# PWM_schematic_2022-05-03.net
KiCad netlist of a schematic drawn in Altium Designer
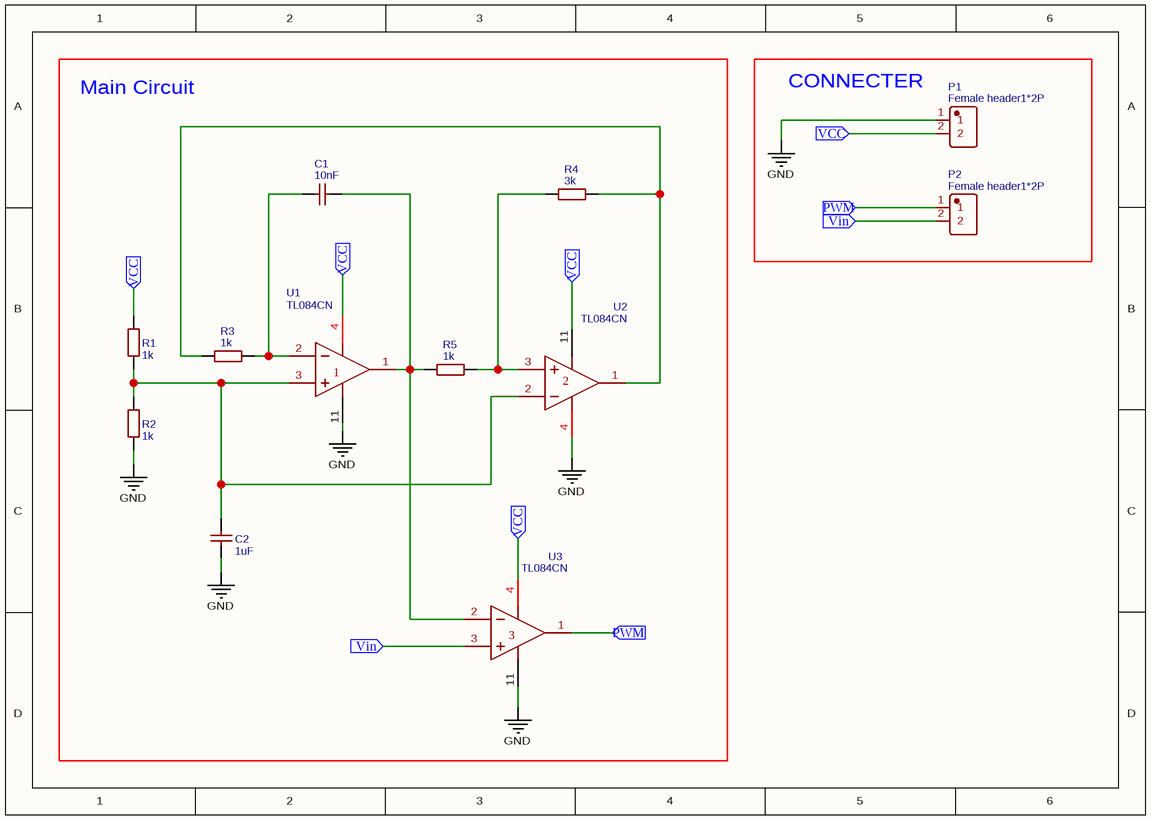
[diagram p0: PWM_schematic_2022-05-03.schdoc]

(export (version "E")
  (design (tool "Eeschema 10.0.6"))
  (components
    (comp (ref "C1")
      (value "10nF")
      (fields
        (field (name "BOM_MANUFACTURER PART") "22pf/50V 10%")
        (field (name "BOM_SUPPLIER PART") "C9316")
      )
      (libsource (lib "altium-import") (part "root_0_10nF_"))
    )
    (comp (ref "C2")
      (value "1uF")
      (fields
        (field (name "BOM_MANUFACTURER PART") "22pf/50V 10%")
        (field (name "BOM_SUPPLIER PART") "C9316")
      )
      (libsource (lib "altium-import") (part "root_1_1uF_"))
    )
    (comp (ref "P1")
      (value "Female header1*2P")
      (fields (field (name "BOM_SUPPLIER PART") "C66509"))
      (libsource (lib "altium-import") (part "root_0_Female header1*2P_"))
    )
    (comp (ref "P2")
      (value "Female header1*2P")
      (fields (field (name "BOM_SUPPLIER PART") "C66509"))
      (libsource (lib "altium-import") (part "root_0_Female header1*2P_"))
    )
    (comp (ref "R1")
      (value "1k")
      (fields
        (field (name "POWER") "1/4W")
        (field (name "TOLERANCE") "±1%")
        (field (name "BOM_SUPPLIER PART") "E57439")
      )
      (libsource (lib "altium-import") (part "root_1_1k_"))
    )
    (comp (ref "R2")
      (value "1k")
      (fields
        (field (name "POWER") "1/4W")
        (field (name "TOLERANCE") "±1%")
        (field (name "BOM_SUPPLIER PART") "E57439")
      )
      (libsource (lib "altium-import") (part "root_1_1k_"))
    )
    (comp (ref "R3")
      (value "1k")
      (fields
        (field (name "POWER") "1/4W")
        (field (name "TOLERANCE") "±1%")
        (field (name "BOM_SUPPLIER PART") "E57439")
      )
      (libsource (lib "altium-import") (part "root_0_1k_"))
    )
    (comp (ref "R4")
      (value "3k")
      (fields
        (field (name "POWER") "1/4W")
        (field (name "TOLERANCE") "±1%")
        (field (name "BOM_SUPPLIER PART") "E57439")
      )
      (libsource (lib "altium-import") (part "root_0_3k_"))
    )
    (comp (ref "R5")
      (value "1k")
      (fields
        (field (name "POWER") "1/4W")
        (field (name "TOLERANCE") "±1%")
        (field (name "BOM_SUPPLIER PART") "E57439")
      )
      (libsource (lib "altium-import") (part "root_0_1k_"))
    )
    (comp (ref "U1")
      (value "TL084CN")
      (fields
        (field (name "BOM_SUPPLIER PART") "C5163")
        (field (name "BOM_MANUFACTURER PART") "STMicroelectronics")
        (field (name "SUBPART_NO") "1")
      )
      (libsource (lib "altium-import") (part "root_0_TL084CN_"))
    )
    (comp (ref "U2")
      (value "TL084CN")
      (fields
        (field (name "BOM_SUPPLIER PART") "C5163")
        (field (name "BOM_MANUFACTURER PART") "STMicroelectronics")
        (field (name "SUBPART_NO") "1")
      )
      (libsource (lib "altium-import") (part "root_2_TL084CN_"))
    )
    (comp (ref "U3")
      (value "TL084CN")
      (fields
        (field (name "BOM_SUPPLIER PART") "C5163")
        (field (name "BOM_MANUFACTURER PART") "STMicroelectronics")
        (field (name "SUBPART_NO") "1")
      )
      (libsource (lib "altium-import") (part "root_0_TL084CN_"))
    )
  )
  (nets
    (net (code "1") (name "/PWM") (class "Default")
      (node (ref "P2") (pin "1") (pinfunction "1_1") (pintype "passive"))
      (node (ref "U3") (pin "1") (pinfunction "OUT_1") (pintype "passive"))
    )
    (net (code "2") (name "/VCC") (class "Default")
      (node (ref "P1") (pin "2") (pinfunction "2_2") (pintype "passive"))
      (node (ref "R1") (pin "2") (pinfunction "2_2") (pintype "passive"))
      (node (ref "U1") (pin "4") (pinfunction "V+_4") (pintype "passive"))
      (node (ref "U2") (pin "11") (pinfunction "V-_11") (pintype "passive"))
      (node (ref "U3") (pin "4") (pinfunction "V+_4") (pintype "passive"))
    )
    (net (code "3") (name "/Vin") (class "Default")
      (node (ref "P2") (pin "2") (pinfunction "2_2") (pintype "passive"))
      (node (ref "U3") (pin "3") (pinfunction "IN+_3") (pintype "passive"))
    )
    (net (code "4") (name "GND") (class "Default")
      (node (ref "C2") (pin "1") (pinfunction "1_1") (pintype "passive"))
      (node (ref "P1") (pin "1") (pinfunction "1_1") (pintype "passive"))
      (node (ref "R2") (pin "1") (pinfunction "1_1") (pintype "passive"))
      (node (ref "U1") (pin "11") (pinfunction "V-_11") (pintype "passive"))
      (node (ref "U2") (pin "4") (pinfunction "V+_4") (pintype "passive"))
      (node (ref "U3") (pin "11") (pinfunction "V-_11") (pintype "passive"))
    )
    (net (code "5") (name "Net-(U1-IN+)") (class "Default")
      (node (ref "C2") (pin "2") (pinfunction "2_2") (pintype "passive"))
      (node (ref "R1") (pin "1") (pinfunction "1_1") (pintype "passive"))
      (node (ref "R2") (pin "2") (pinfunction "2_2") (pintype "passive"))
      (node (ref "U1") (pin "3") (pinfunction "IN+_3") (pintype "passive"))
      (node (ref "U2") (pin "2") (pinfunction "IN-_2") (pintype "passive"))
    )
    (net (code "6") (name "Net-(U1-IN-)") (class "Default")
      (node (ref "C1") (pin "1") (pinfunction "1_1") (pintype "passive"))
      (node (ref "R3") (pin "2") (pinfunction "2_2") (pintype "passive"))
      (node (ref "U1") (pin "2") (pinfunction "IN-_2") (pintype "passive"))
    )
    (net (code "7") (name "Net-(U1-OUT)") (class "Default")
      (node (ref "C1") (pin "2") (pinfunction "2_2") (pintype "passive"))
      (node (ref "R5") (pin "1") (pinfunction "1_1") (pintype "passive"))
      (node (ref "U1") (pin "1") (pinfunction "OUT_1") (pintype "passive"))
      (node (ref "U3") (pin "2") (pinfunction "IN-_2") (pintype "passive"))
    )
    (net (code "8") (name "Net-(U2-IN+)") (class "Default")
      (node (ref "R4") (pin "1") (pinfunction "1_1") (pintype "passive"))
      (node (ref "R5") (pin "2") (pinfunction "2_2") (pintype "passive"))
      (node (ref "U2") (pin "3") (pinfunction "IN+_3") (pintype "passive"))
    )
    (net (code "9") (name "Net-(U2-OUT)") (class "Default")
      (node (ref "R3") (pin "1") (pinfunction "1_1") (pintype "passive"))
      (node (ref "R4") (pin "2") (pinfunction "2_2") (pintype "passive"))
      (node (ref "U2") (pin "1") (pinfunction "OUT_1") (pintype "passive"))
    )
  )
)
